# 01_Leonardo_Rev3d.net
KiCad netlist of a schematic drawn in Altium Designer
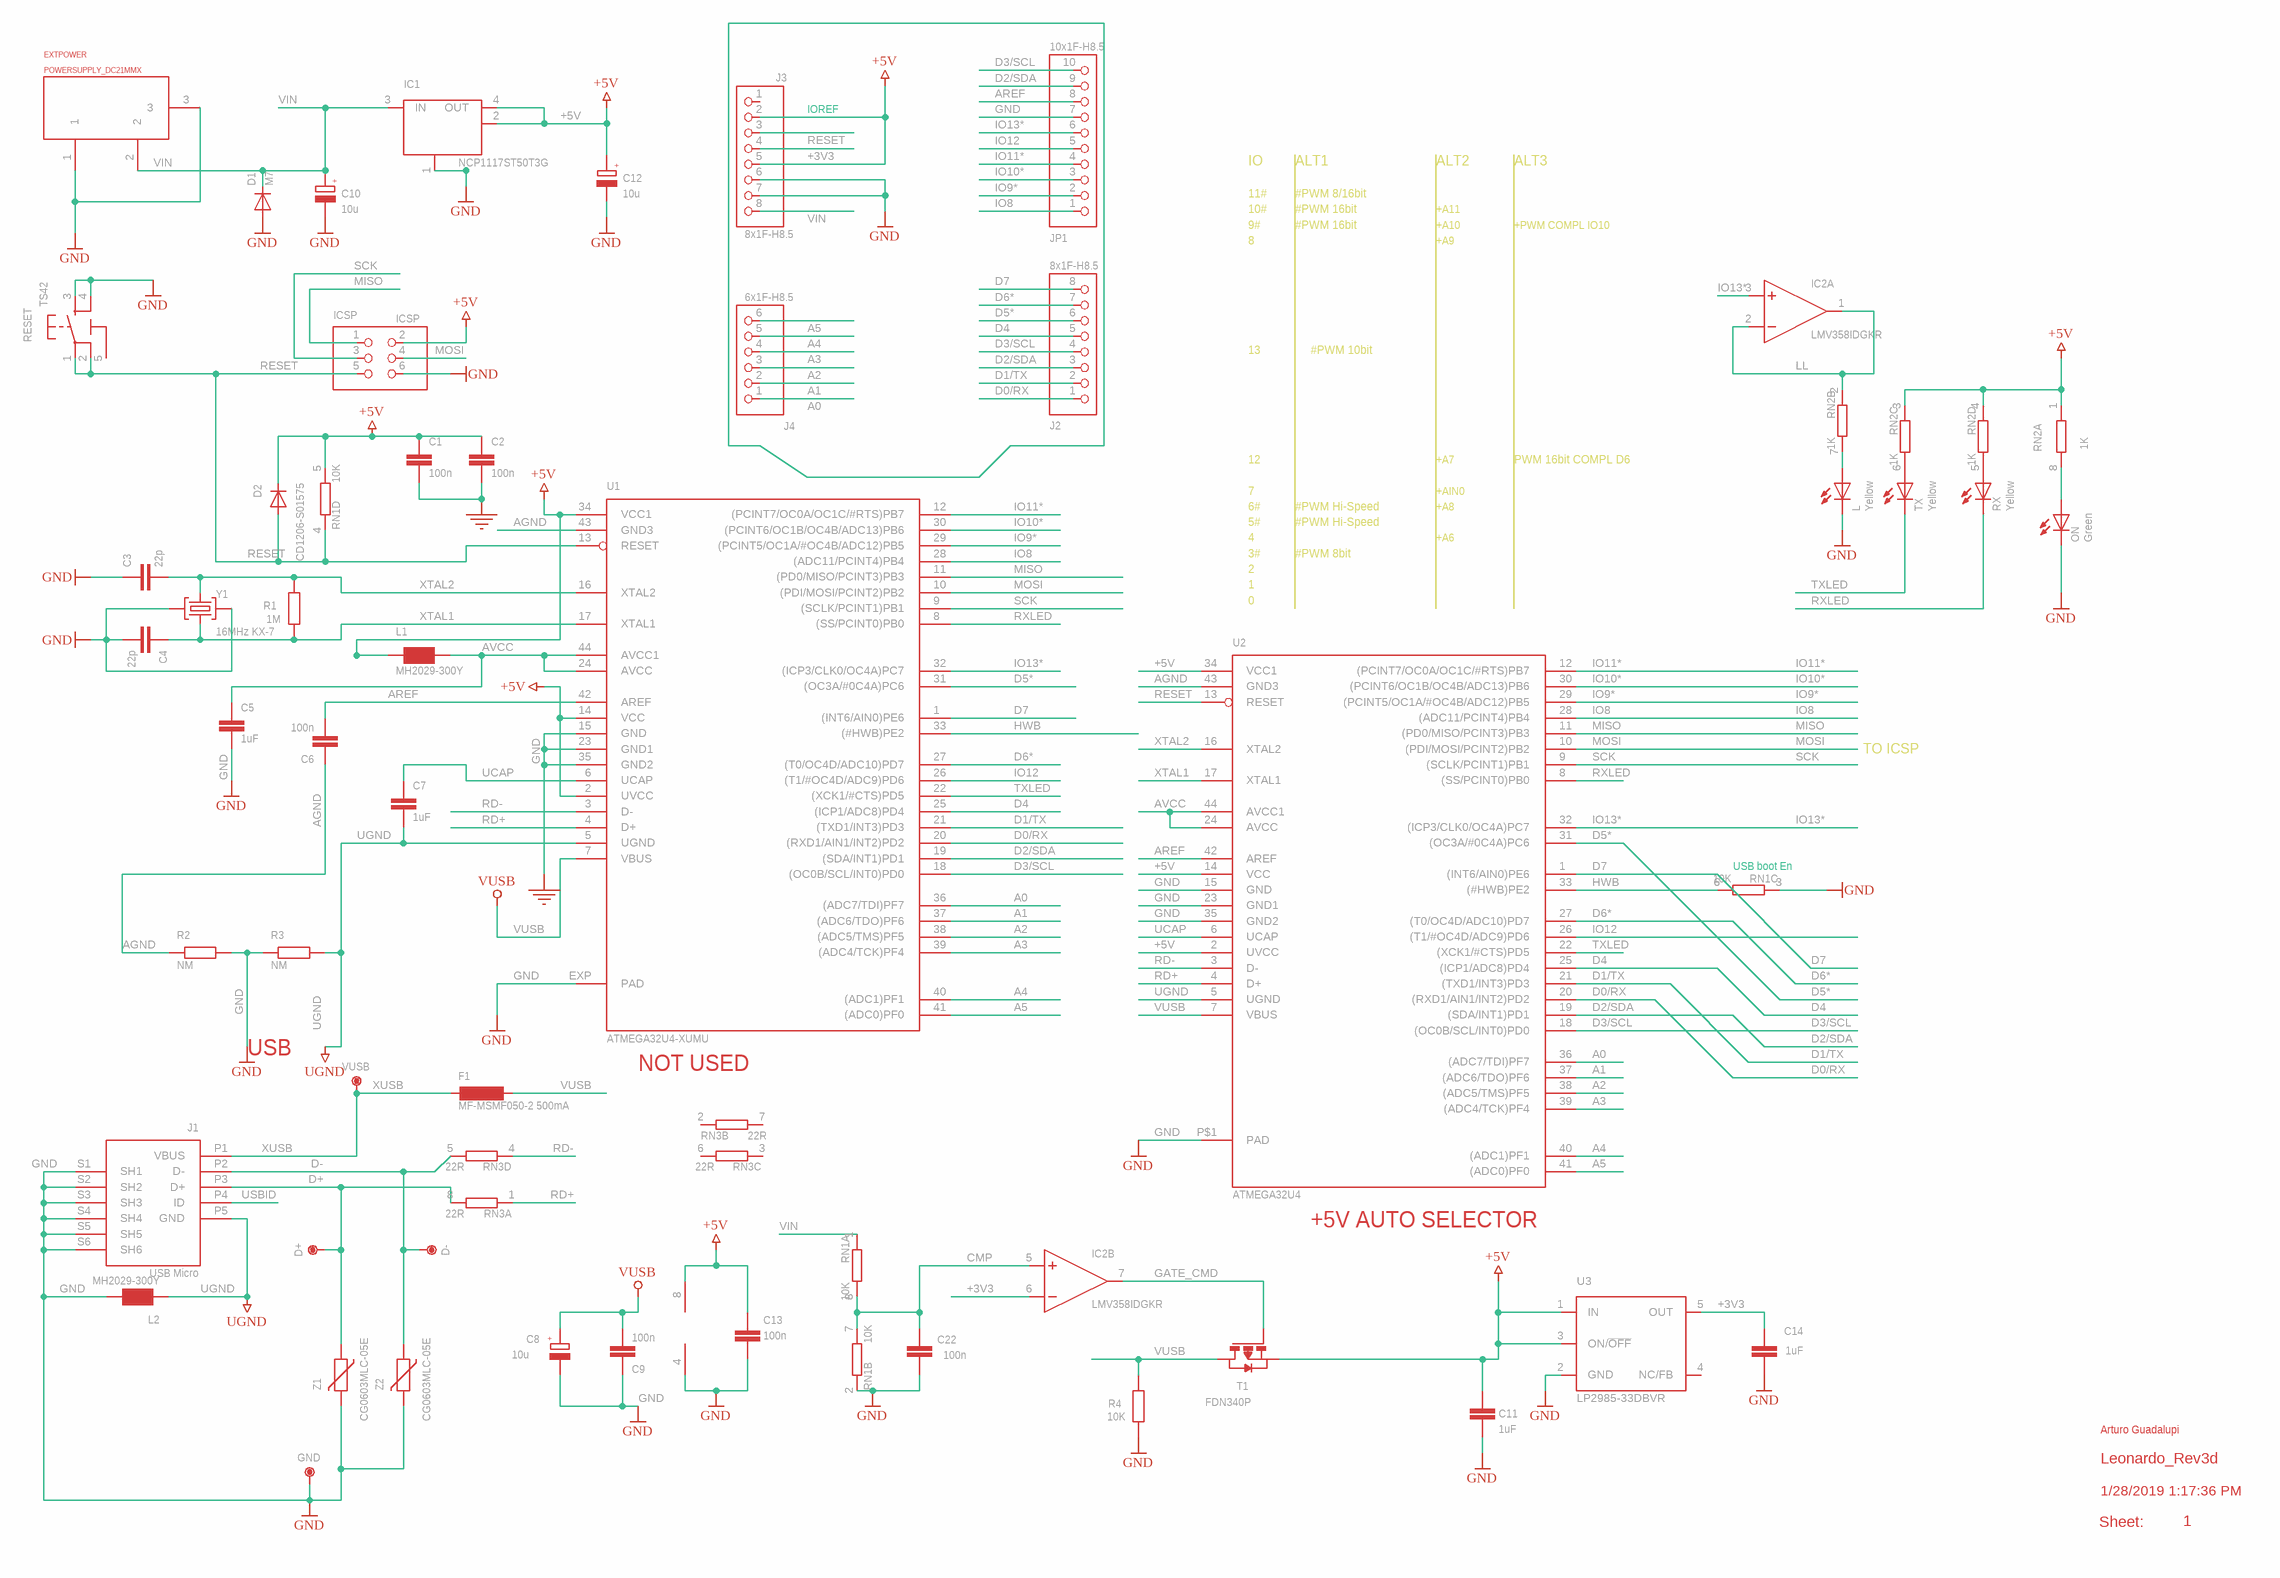
[diagram p0: 01.Leonardo_Rev3d.SchDoc]

(export (version "E")
  (design (tool "Eeschema 10.0.6"))
  (components
    (comp (ref "C1")
      (value "100n")
      (footprint "C0603-ROUND")
      (description "CAPACITOR, European symbol")
      (libsource (lib "") (part "C-EUC0603_2"))
    )
    (comp (ref "C2")
      (value "100n")
      (footprint "C0603-ROUND")
      (description "CAPACITOR, European symbol")
      (libsource (lib "") (part "C-EUC0603_2"))
    )
    (comp (ref "C3")
      (value "22p")
      (footprint "C0603-ROUND")
      (description "CAPACITOR, European symbol")
      (libsource (lib "") (part "C-EUC0603_1"))
    )
    (comp (ref "C4")
      (value "22p")
      (footprint "C0603-ROUND")
      (description "CAPACITOR, European symbol")
      (libsource (lib "") (part "C-EUC0603_3"))
    )
    (comp (ref "C5")
      (value "1uF")
      (footprint "C0603-ROUND")
      (description "CAPACITOR, European symbol")
      (libsource (lib "") (part "C-EUC0603_2"))
    )
    (comp (ref "C6")
      (value "100n")
      (footprint "C0603-ROUND")
      (description "CAPACITOR, European symbol")
      (libsource (lib "SmartPrj") (part "C-EUC0603"))
    )
    (comp (ref "C7")
      (value "1uF")
      (footprint "C0603-ROUND")
      (description "CAPACITOR, European symbol")
      (libsource (lib "") (part "C-EUC0603_2"))
    )
    (comp (ref "C8")
      (value "10u")
      (footprint "SMC_B")
      (description "POLARIZED CAPACITOR, European symbol")
      (fields (field (name "+") "+"))
      (libsource (lib "") (part "CPOL-EUSMCB_1"))
    )
    (comp (ref "C9")
      (value "100n")
      (footprint "C0603-ROUND")
      (description "CAPACITOR, European symbol")
      (libsource (lib "") (part "C-EUC0603_1"))
    )
    (comp (ref "C10")
      (value "10u")
      (footprint "SMC_B")
      (description "POLARIZED CAPACITOR, European symbol")
      (fields (field (name "+") "+"))
      (libsource (lib "rcl") (part "CPOL-EUSMCB"))
    )
    (comp (ref "C11")
      (value "1uF")
      (footprint "C0603-ROUND")
      (description "CAPACITOR, European symbol")
      (libsource (lib "") (part "C-EUC0603_1"))
    )
    (comp (ref "C12")
      (value "10u")
      (footprint "SMC_B")
      (description "POLARIZED CAPACITOR, European symbol")
      (fields (field (name "+") "+"))
      (libsource (lib "rcl") (part "CPOL-EUSMCB"))
    )
    (comp (ref "C13")
      (value "100n")
      (footprint "C0603-ROUND")
      (description "CAPACITOR, European symbol")
      (libsource (lib "") (part "C-EUC0603_2"))
    )
    (comp (ref "C14")
      (value "1uF")
      (footprint "C0603-ROUND")
      (description "CAPACITOR, European symbol")
      (libsource (lib "SmartPrj") (part "C-EUC0603"))
    )
    (comp (ref "C22")
      (value "100n")
      (footprint "C0603-ROUND")
      (description "CAPACITOR, European symbol")
      (libsource (lib "") (part "C-EUC0603_1"))
    )
    (comp (ref "D+")
      (value "DNP")
      (footprint "TP-1.00MM")
      (description "Testpoint")
      (libsource (lib "Arduino-utility") (part "TPTP-1.00MM"))
    )
    (comp (ref "D-")
      (value "DNP")
      (footprint "TP-1.00MM")
      (description "Testpoint")
      (libsource (lib "Arduino-utility") (part "TPTP-1.00MM"))
    )
    (comp (ref "D1")
      (value "M7")
      (footprint "SMB")
      (description "DIODE")
      (libsource (lib "diode") (part "DIODE-SMB"))
    )
    (comp (ref "D2")
      (value "CD1206-S01575")
      (footprint "MINIMELF")
      (description "DIODE")
      (libsource (lib "diode") (part "DIODE-MINIMELF"))
    )
    (comp (ref "EXTPOWER")
      (value "POWERSUPPLY_DC21MMX")
      (footprint "POWERSUPPLY_DC-21MM")
      (libsource (lib "SmartPrj") (part "POWERSUPPLY_DC21MMX"))
    )
    (comp (ref "F1")
      (value "MF-MSMF050-2 500mA")
      (footprint "L1812")
      (description "INDUCTOR, European symbol")
      (libsource (lib "rcl") (part "L-EUL1812"))
    )
    (comp (ref "GND")
      (value "DNP")
      (footprint "TP-1.00MM")
      (description "Testpoint")
      (libsource (lib "Arduino-utility") (part "TPTP-1.00MM"))
    )
    (comp (ref "IC1")
      (value "NCP1117ST50T3G")
      (footprint "SOT223")
      (libsource (lib "linear") (part "MC33269ST*"))
    )
    (comp (ref "IC2")
      (value "LMV358IDGKR")
      (footprint "MSOP08")
      (libsource (lib "linear") (part "LMV358?*MM"))
    )
    (comp (ref "ICSP")
      (value "ICSP")
      (footprint "2X03")
      (description "PIN HEADER")
      (libsource (lib "SmartPrj") (part "PINHD-2X3"))
    )
    (comp (ref "J1")
      (value "USB Micro")
      (footprint "CON2_USB_MICRO_B_AT")
      (fields (field (name "MANUFACTURER") "FCI"))
      (libsource (lib "Arduino-connectors") (part "USB-MICRO-LEGACY"))
    )
    (comp (ref "J2")
      (value "8x1F-H8.5")
      (footprint "1X08")
      (description "PIN HEADER")
      (libsource (lib "SmartPrj") (part "PINHD-1X8"))
    )
    (comp (ref "J3")
      (value "8x1F-H8.5")
      (footprint "1X08")
      (description "PIN HEADER")
      (libsource (lib "SmartPrj") (part "PINHD-1X8"))
    )
    (comp (ref "J4")
      (value "6x1F-H8.5")
      (footprint "1X06")
      (description "PIN HEADER")
      (libsource (lib "SmartPrj") (part "PINHD-1X6"))
    )
    (comp (ref "JP1")
      (value "10x1F-H8.5")
      (footprint "1X10")
      (description "PIN HEADER")
      (libsource (lib "SmartPrj") (part "PINHD-1X10"))
    )
    (comp (ref "L")
      (value "Yellow")
      (footprint "CHIPLED_0805")
      (libsource (lib "led") (part "LEDCHIPLED_0805"))
    )
    (comp (ref "L1") (value "MH2029-300Y") (footprint "0805") (libsource (lib "") (part "WE-CBF_0805_1")))
    (comp (ref "L2")
      (value "MH2029-300Y")
      (footprint "0805")
      (libsource (lib "wuerth-elektronik") (part "WE-CBF_0805"))
    )
    (comp (ref "ON")
      (value "Green")
      (footprint "CHIPLED_0805")
      (libsource (lib "led") (part "LEDCHIPLED_0805"))
    )
    (comp (ref "R1")
      (value "1M")
      (footprint "R0603-ROUND")
      (description "RESISTOR, European symbol")
      (libsource (lib "SmartPrj") (part "R-EU_R0603"))
    )
    (comp (ref "R2")
      (value "NM")
      (footprint "R0402")
      (description "RESISTOR, European symbol")
      (libsource (lib "SmartPrj") (part "R-EU_R0402"))
    )
    (comp (ref "R3")
      (value "NM")
      (footprint "R0402")
      (description "RESISTOR, European symbol")
      (libsource (lib "SmartPrj") (part "R-EU_R0402"))
    )
    (comp (ref "R4")
      (value "10K")
      (footprint "R0603-ROUND")
      (description "RESISTOR, European symbol")
      (libsource (lib "SmartPrj") (part "R-EU_R0603"))
    )
    (comp (ref "RESET")
      (value "TS42")
      (footprint "TS42")
      (description "TS42 Dongnan Electronics Tact switch VDC 12V - 50mA")
      (libsource (lib "SmartPrj") (part "TS42"))
    )
    (comp (ref "RN1")
      (value "10K")
      (footprint "CAY16")
      (description "Array Chip Resistor   Source: RS Component / Phycomp")
      (fields (field (name "LIBRARYNAME") "resistor-dil"))
      (libsource (lib "resistor-dil") (part "4R-NCAY16"))
    )
    (comp (ref "RN2")
      (value "1K")
      (footprint "CAY16")
      (description "Array Chip Resistor   Source: RS Component / Phycomp")
      (fields (field (name "LIBRARYNAME") "resistor-dil"))
      (libsource (lib "resistor-dil") (part "4R-NCAY16"))
    )
    (comp (ref "RN3")
      (value "22R")
      (footprint "CAY16")
      (description "Array Chip Resistor   Source: RS Component / Phycomp")
      (fields (field (name "LIBRARYNAME") "resistor-dil"))
      (libsource (lib "resistor-dil") (part "4R-NCAY16"))
    )
    (comp (ref "RX")
      (value "Yellow")
      (footprint "CHIPLED_0805")
      (libsource (lib "led") (part "LEDCHIPLED_0805"))
    )
    (comp (ref "T1")
      (value "FDN340P")
      (footprint "SOT-23")
      (description "MOS FET")
      (libsource (lib "zetex") (part "PMOSSOT23"))
    )
    (comp (ref "TX")
      (value "Yellow")
      (footprint "CHIPLED_0805")
      (libsource (lib "led") (part "LEDCHIPLED_0805"))
    )
    (comp (ref "U1")
      (value "ATMEGA32U4-XUMU")
      (footprint "QFN44ML7X7")
      (libsource (lib "SmartPrj") (part "ATMEGA32U4-XUMU"))
    )
    (comp (ref "U2")
      (value "ATMEGA32U4")
      (footprint "TQFP44-PAD")
      (libsource (lib "SmartPrj") (part "ATMEGA32U4-XUAU"))
    )
    (comp (ref "U3")
      (value "LP2985-33DBVR")
      (footprint "SOT23-DBV")
      (libsource (lib "SmartPrj") (part "LP2985-XXDBVR"))
    )
    (comp (ref "VUSB")
      (value "DNP")
      (footprint "TP-1.00MM")
      (description "Testpoint")
      (libsource (lib "Arduino-utility") (part "TPTP-1.00MM"))
    )
    (comp (ref "Y1")
      (value "16MHz KX-7")
      (footprint "CRYSTAL-3.2-2.5")
      (libsource (lib "SmartPrj") (part "CRYSTAL-3.2-2.5"))
    )
    (comp (ref "Z1")
      (value "CG0603MLC-05E")
      (footprint "CT/CN0603")
      (description "VARISTOR")
      (libsource (lib "varistor") (part "VARISTORCN0603"))
    )
    (comp (ref "Z2")
      (value "CG0603MLC-05E")
      (footprint "CT/CN0603")
      (description "VARISTOR")
      (libsource (lib "varistor") (part "VARISTORCN0603"))
    )
  )
  (nets
    (net (code "1") (name "+5V") (class "Default")
      (node (ref "C1") (pin "1") (pinfunction "1_1") (pintype "passive"))
      (node (ref "C11") (pin "2") (pinfunction "2_2") (pintype "passive"))
      (node (ref "C12") (pin "+") (pinfunction "+_+") (pintype "passive"))
      (node (ref "C13") (pin "1") (pinfunction "1_1") (pintype "passive"))
      (node (ref "C2") (pin "1") (pinfunction "1_1") (pintype "passive"))
      (node (ref "D2") (pin "C") (pinfunction "C_C") (pintype "passive"))
      (node (ref "IC1") (pin "2") (pinfunction "OUT_2") (pintype "passive"))
      (node (ref "IC1") (pin "4") (pinfunction "OUT_4") (pintype "passive"))
      (node (ref "IC2") (pin "8") (pinfunction "V+_8") (pintype "passive"))
      (node (ref "ICSP") (pin "2") (pinfunction "2_2") (pintype "passive"))
      (node (ref "J3") (pin "2") (pinfunction "2_2") (pintype "passive"))
      (node (ref "J3") (pin "5") (pinfunction "5_5") (pintype "passive"))
      (node (ref "L1") (pin "1") (pinfunction "1_1") (pintype "passive"))
      (node (ref "RN1") (pin "5") (pinfunction "2_5") (pintype "passive"))
      (node (ref "RN2") (pin "1") (pinfunction "1_1") (pintype "passive"))
      (node (ref "RN2") (pin "3") (pinfunction "1_3") (pintype "passive"))
      (node (ref "RN2") (pin "4") (pinfunction "1_4") (pintype "passive"))
      (node (ref "T1") (pin "2") (pinfunction "S_2") (pintype "passive"))
      (node (ref "U1") (pin "14") (pinfunction "VCC_14") (pintype "passive"))
      (node (ref "U1") (pin "2") (pinfunction "UVCC_2") (pintype "passive"))
      (node (ref "U1") (pin "34") (pinfunction "VCC1_34") (pintype "passive"))
      (node (ref "U2") (pin "14") (pinfunction "VCC_14") (pintype "passive"))
      (node (ref "U2") (pin "2") (pinfunction "UVCC_2") (pintype "passive"))
      (node (ref "U2") (pin "34") (pinfunction "VCC1_34") (pintype "passive"))
      (node (ref "U3") (pin "1") (pinfunction "IN_1") (pintype "passive"))
      (node (ref "U3") (pin "3") (pinfunction "ON/~{OFF}_3") (pintype "passive"))
    )
    (net (code "2") (name "/+3V3") (class "Default")
      (node (ref "C14") (pin "2") (pinfunction "2_2") (pintype "passive"))
      (node (ref "IC2") (pin "6") (pinfunction "-IN_6") (pintype "passive"))
      (node (ref "J3") (pin "4") (pinfunction "4_4") (pintype "passive"))
      (node (ref "U3") (pin "5") (pinfunction "OUT_5") (pintype "passive"))
    )
    (net (code "3") (name "/A0") (class "Default")
      (node (ref "J4") (pin "1") (pinfunction "1_1") (pintype "passive"))
      (node (ref "U1") (pin "36") (pinfunction "(ADC7/TDI)PF7_36") (pintype "passive"))
      (node (ref "U2") (pin "36") (pinfunction "(ADC7/TDI)PF7_36") (pintype "passive"))
    )
    (net (code "4") (name "/A1") (class "Default")
      (node (ref "J4") (pin "2") (pinfunction "2_2") (pintype "passive"))
      (node (ref "U1") (pin "37") (pinfunction "(ADC6/TDO)PF6_37") (pintype "passive"))
      (node (ref "U2") (pin "37") (pinfunction "(ADC6/TDO)PF6_37") (pintype "passive"))
    )
    (net (code "5") (name "/A2") (class "Default")
      (node (ref "J4") (pin "3") (pinfunction "3_3") (pintype "passive"))
      (node (ref "U1") (pin "38") (pinfunction "(ADC5/TMS)PF5_38") (pintype "passive"))
      (node (ref "U2") (pin "38") (pinfunction "(ADC5/TMS)PF5_38") (pintype "passive"))
    )
    (net (code "6") (name "/A3") (class "Default")
      (node (ref "J4") (pin "4") (pinfunction "4_4") (pintype "passive"))
      (node (ref "U1") (pin "39") (pinfunction "(ADC4/TCK)PF4_39") (pintype "passive"))
      (node (ref "U2") (pin "39") (pinfunction "(ADC4/TCK)PF4_39") (pintype "passive"))
    )
    (net (code "7") (name "/A4") (class "Default")
      (node (ref "J4") (pin "5") (pinfunction "5_5") (pintype "passive"))
      (node (ref "U1") (pin "40") (pinfunction "(ADC1)PF1_40") (pintype "passive"))
      (node (ref "U2") (pin "40") (pinfunction "(ADC1)PF1_40") (pintype "passive"))
    )
    (net (code "8") (name "/A5") (class "Default")
      (node (ref "J4") (pin "6") (pinfunction "6_6") (pintype "passive"))
      (node (ref "U1") (pin "41") (pinfunction "(ADC0)PF0_41") (pintype "passive"))
      (node (ref "U2") (pin "41") (pinfunction "(ADC0)PF0_41") (pintype "passive"))
    )
    (net (code "9") (name "/AGND") (class "Default")
      (node (ref "C6") (pin "1") (pinfunction "1_1") (pintype "passive"))
      (node (ref "R2") (pin "1") (pinfunction "1_1") (pintype "passive"))
      (node (ref "U1") (pin "43") (pinfunction "GND3_43") (pintype "passive"))
      (node (ref "U2") (pin "43") (pinfunction "GND3_43") (pintype "passive"))
    )
    (net (code "10") (name "/AREF") (class "Default")
      (node (ref "C6") (pin "2") (pinfunction "2_2") (pintype "passive"))
      (node (ref "JP1") (pin "8") (pinfunction "8_8") (pintype "passive"))
      (node (ref "U1") (pin "42") (pinfunction "AREF_42") (pintype "passive"))
      (node (ref "U2") (pin "42") (pinfunction "AREF_42") (pintype "passive"))
    )
    (net (code "11") (name "/AVCC") (class "Default")
      (node (ref "C5") (pin "1") (pinfunction "1_1") (pintype "passive"))
      (node (ref "L1") (pin "2") (pinfunction "2_2") (pintype "passive"))
      (node (ref "U1") (pin "24") (pinfunction "AVCC_24") (pintype "passive"))
      (node (ref "U1") (pin "44") (pinfunction "AVCC1_44") (pintype "passive"))
      (node (ref "U2") (pin "24") (pinfunction "AVCC_24") (pintype "passive"))
      (node (ref "U2") (pin "44") (pinfunction "AVCC1_44") (pintype "passive"))
    )
    (net (code "12") (name "/CMP") (class "Default")
      (node (ref "C22") (pin "2") (pinfunction "2_2") (pintype "passive"))
      (node (ref "IC2") (pin "5") (pinfunction "+IN_5") (pintype "passive"))
      (node (ref "RN1") (pin "7") (pinfunction "2_7") (pintype "passive"))
      (node (ref "RN1") (pin "8") (pinfunction "2_8") (pintype "passive"))
    )
    (net (code "13") (name "/D+") (class "Default")
      (node (ref "D+") (pin "X") (pinfunction "P$1_X") (pintype "passive"))
      (node (ref "J1") (pin "P3") (pinfunction "D+_P3") (pintype "passive"))
      (node (ref "RN3") (pin "8") (pinfunction "2_8") (pintype "passive"))
      (node (ref "Z1") (pin "1") (pinfunction "1_1") (pintype "passive"))
    )
    (net (code "14") (name "/D-") (class "Default")
      (node (ref "D-") (pin "X") (pinfunction "P$1_X") (pintype "passive"))
      (node (ref "J1") (pin "P2") (pinfunction "D-_P2") (pintype "passive"))
      (node (ref "RN3") (pin "5") (pinfunction "2_5") (pintype "passive"))
      (node (ref "Z2") (pin "1") (pinfunction "1_1") (pintype "passive"))
    )
    (net (code "15") (name "/D0{slash}RX") (class "Default")
      (node (ref "J2") (pin "1") (pinfunction "1_1") (pintype "passive"))
      (node (ref "U1") (pin "20") (pinfunction "(RXD1/AIN1/INT2)PD2_20") (pintype "passive"))
      (node (ref "U2") (pin "20") (pinfunction "(RXD1/AIN1/INT2)PD2_20") (pintype "passive"))
    )
    (net (code "16") (name "/D1{slash}TX") (class "Default")
      (node (ref "J2") (pin "2") (pinfunction "2_2") (pintype "passive"))
      (node (ref "U1") (pin "21") (pinfunction "(TXD1/INT3)PD3_21") (pintype "passive"))
      (node (ref "U2") (pin "21") (pinfunction "(TXD1/INT3)PD3_21") (pintype "passive"))
    )
    (net (code "17") (name "/D2{slash}SDA") (class "Default")
      (node (ref "J2") (pin "3") (pinfunction "3_3") (pintype "passive"))
      (node (ref "JP1") (pin "9") (pinfunction "9_9") (pintype "passive"))
      (node (ref "U1") (pin "19") (pinfunction "(SDA/INT1)PD1_19") (pintype "passive"))
      (node (ref "U2") (pin "19") (pinfunction "(SDA/INT1)PD1_19") (pintype "passive"))
    )
    (net (code "18") (name "/D3{slash}SCL") (class "Default")
      (node (ref "J2") (pin "4") (pinfunction "4_4") (pintype "passive"))
      (node (ref "JP1") (pin "10") (pinfunction "10_10") (pintype "passive"))
      (node (ref "U1") (pin "18") (pinfunction "(OC0B/SCL/INT0)PD0_18") (pintype "passive"))
      (node (ref "U2") (pin "18") (pinfunction "(OC0B/SCL/INT0)PD0_18") (pintype "passive"))
    )
    (net (code "19") (name "/D4") (class "Default")
      (node (ref "J2") (pin "5") (pinfunction "5_5") (pintype "passive"))
      (node (ref "U1") (pin "25") (pinfunction "(ICP1/ADC8)PD4_25") (pintype "passive"))
      (node (ref "U2") (pin "25") (pinfunction "(ICP1/ADC8)PD4_25") (pintype "passive"))
    )
    (net (code "20") (name "/D5*") (class "Default")
      (node (ref "J2") (pin "6") (pinfunction "6_6") (pintype "passive"))
      (node (ref "U1") (pin "31") (pinfunction "(OC3A/#0C4A)PC6_31") (pintype "passive"))
      (node (ref "U2") (pin "31") (pinfunction "(OC3A/#0C4A)PC6_31") (pintype "passive"))
    )
    (net (code "21") (name "/D6*") (class "Default")
      (node (ref "J2") (pin "7") (pinfunction "7_7") (pintype "passive"))
      (node (ref "U1") (pin "27") (pinfunction "(T0/OC4D/ADC10)PD7_27") (pintype "passive"))
      (node (ref "U2") (pin "27") (pinfunction "(T0/OC4D/ADC10)PD7_27") (pintype "passive"))
    )
    (net (code "22") (name "/D7") (class "Default")
      (node (ref "J2") (pin "8") (pinfunction "8_8") (pintype "passive"))
      (node (ref "U1") (pin "1") (pinfunction "(INT6/AIN0)PE6_1") (pintype "passive"))
      (node (ref "U2") (pin "1") (pinfunction "(INT6/AIN0)PE6_1") (pintype "passive"))
    )
    (net (code "23") (name "/GATE_CMD") (class "Default")
      (node (ref "IC2") (pin "7") (pinfunction "OUT_7") (pintype "passive"))
      (node (ref "T1") (pin "3") (pinfunction "G_3") (pintype "passive"))
    )
    (net (code "24") (name "/HWB") (class "Default")
      (node (ref "RN1") (pin "6") (pinfunction "2_6") (pintype "passive"))
      (node (ref "U1") (pin "33") (pinfunction "(#HWB)PE2_33") (pintype "passive"))
      (node (ref "U2") (pin "33") (pinfunction "(#HWB)PE2_33") (pintype "passive"))
    )
    (net (code "25") (name "/IO8") (class "Default")
      (node (ref "JP1") (pin "1") (pinfunction "1_1") (pintype "passive"))
      (node (ref "U1") (pin "28") (pinfunction "(ADC11/PCINT4)PB4_28") (pintype "passive"))
      (node (ref "U2") (pin "28") (pinfunction "(ADC11/PCINT4)PB4_28") (pintype "passive"))
    )
    (net (code "26") (name "/IO9*") (class "Default")
      (node (ref "JP1") (pin "2") (pinfunction "2_2") (pintype "passive"))
      (node (ref "U1") (pin "29") (pinfunction "(PCINT5/OC1A/#OC4B/ADC12)PB5_29") (pintype "passive"))
      (node (ref "U2") (pin "29") (pinfunction "(PCINT5/OC1A/#OC4B/ADC12)PB5_29") (pintype "passive"))
    )
    (net (code "27") (name "/IO10*") (class "Default")
      (node (ref "JP1") (pin "3") (pinfunction "3_3") (pintype "passive"))
      (node (ref "U1") (pin "30") (pinfunction "(PCINT6/OC1B/OC4B/ADC13)PB6_30") (pintype "passive"))
      (node (ref "U2") (pin "30") (pinfunction "(PCINT6/OC1B/OC4B/ADC13)PB6_30") (pintype "passive"))
    )
    (net (code "28") (name "/IO11*") (class "Default")
      (node (ref "JP1") (pin "4") (pinfunction "4_4") (pintype "passive"))
      (node (ref "U1") (pin "12") (pinfunction "(PCINT7/OC0A/OC1C/#RTS)PB7_12") (pintype "passive"))
      (node (ref "U2") (pin "12") (pinfunction "(PCINT7/OC0A/OC1C/#RTS)PB7_12") (pintype "passive"))
    )
    (net (code "29") (name "/IO12") (class "Default")
      (node (ref "JP1") (pin "5") (pinfunction "5_5") (pintype "passive"))
      (node (ref "U1") (pin "26") (pinfunction "(T1/#OC4D/ADC9)PD6_26") (pintype "passive"))
      (node (ref "U2") (pin "26") (pinfunction "(T1/#OC4D/ADC9)PD6_26") (pintype "passive"))
    )
    (net (code "30") (name "/IO13*") (class "Default")
      (node (ref "IC2") (pin "3") (pinfunction "+IN_3") (pintype "passive"))
      (node (ref "JP1") (pin "6") (pinfunction "6_6") (pintype "passive"))
      (node (ref "U1") (pin "32") (pinfunction "(ICP3/CLK0/OC4A)PC7_32") (pintype "passive"))
      (node (ref "U2") (pin "32") (pinfunction "(ICP3/CLK0/OC4A)PC7_32") (pintype "passive"))
    )
    (net (code "31") (name "/LL") (class "Default")
      (node (ref "IC2") (pin "1") (pinfunction "OUT_1") (pintype "passive"))
      (node (ref "IC2") (pin "2") (pinfunction "-IN_2") (pintype "passive"))
      (node (ref "RN2") (pin "2") (pinfunction "1_2") (pintype "passive"))
    )
    (net (code "32") (name "/MISO") (class "Default")
      (node (ref "ICSP") (pin "1") (pinfunction "1_1") (pintype "passive"))
      (node (ref "U1") (pin "11") (pinfunction "(PD0/MISO/PCINT3)PB3_11") (pintype "passive"))
      (node (ref "U2") (pin "11") (pinfunction "(PD0/MISO/PCINT3)PB3_11") (pintype "passive"))
    )
    (net (code "33") (name "/MOSI") (class "Default")
      (node (ref "ICSP") (pin "4") (pinfunction "4_4") (pintype "passive"))
      (node (ref "U1") (pin "10") (pinfunction "(PDI/MOSI/PCINT2)PB2_10") (pintype "passive"))
      (node (ref "U2") (pin "10") (pinfunction "(PDI/MOSI/PCINT2)PB2_10") (pintype "passive"))
    )
    (net (code "34") (name "/RD+") (class "Default")
      (node (ref "RN3") (pin "1") (pinfunction "1_1") (pintype "passive"))
      (node (ref "U1") (pin "4") (pinfunction "D+_4") (pintype "passive"))
      (node (ref "U2") (pin "4") (pinfunction "D+_4") (pintype "passive"))
    )
    (net (code "35") (name "/RD-") (class "Default")
      (node (ref "RN3") (pin "4") (pinfunction "1_4") (pintype "passive"))
      (node (ref "U1") (pin "3") (pinfunction "D-_3") (pintype "passive"))
      (node (ref "U2") (pin "3") (pinfunction "D-_3") (pintype "passive"))
    )
    (net (code "36") (name "/RESET") (class "Default")
      (node (ref "D2") (pin "A") (pinfunction "A_A") (pintype "passive"))
      (node (ref "ICSP") (pin "5") (pinfunction "5_5") (pintype "passive"))
      (node (ref "J3") (pin "3") (pinfunction "3_3") (pintype "passive"))
      (node (ref "RESET") (pin "1") (pinfunction "1_1") (pintype "passive"))
      (node (ref "RESET") (pin "2") (pinfunction "2_2") (pintype "passive"))
      (node (ref "RN1") (pin "4") (pinfunction "1_4") (pintype "passive"))
      (node (ref "U1") (pin "13") (pinfunction "RESET_13") (pintype "passive"))
      (node (ref "U2") (pin "13") (pinfunction "RESET_13") (pintype "passive"))
    )
    (net (code "37") (name "/RXLED") (class "Default")
      (node (ref "RX") (pin "C") (pinfunction "C_C") (pintype "passive"))
      (node (ref "U1") (pin "8") (pinfunction "(SS/PCINT0)PB0_8") (pintype "passive"))
      (node (ref "U2") (pin "8") (pinfunction "(SS/PCINT0)PB0_8") (pintype "passive"))
    )
    (net (code "38") (name "/SCK") (class "Default")
      (node (ref "ICSP") (pin "3") (pinfunction "3_3") (pintype "passive"))
      (node (ref "U1") (pin "9") (pinfunction "(SCLK/PCINT1)PB1_9") (pintype "passive"))
      (node (ref "U2") (pin "9") (pinfunction "(SCLK/PCINT1)PB1_9") (pintype "passive"))
    )
    (net (code "39") (name "/TXLED") (class "Default")
      (node (ref "TX") (pin "C") (pinfunction "C_C") (pintype "passive"))
      (node (ref "U1") (pin "22") (pinfunction "(XCK1/#CTS)PD5_22") (pintype "passive"))
      (node (ref "U2") (pin "22") (pinfunction "(XCK1/#CTS)PD5_22") (pintype "passive"))
    )
    (net (code "40") (name "/UCAP") (class "Default")
      (node (ref "C7") (pin "1") (pinfunction "1_1") (pintype "passive"))
      (node (ref "U1") (pin "6") (pinfunction "UCAP_6") (pintype "passive"))
      (node (ref "U2") (pin "6") (pinfunction "UCAP_6") (pintype "passive"))
    )
    (net (code "41") (name "/USBID") (class "Default")
      (node (ref "J1") (pin "P4") (pinfunction "ID_P4") (pintype "passive"))
    )
    (net (code "42") (name "/VIN") (class "Default")
      (node (ref "C10") (pin "+") (pinfunction "+_+") (pintype "passive"))
      (node (ref "D1") (pin "C") (pinfunction "C_C") (pintype "passive"))
      (node (ref "EXTPOWER") (pin "2") (pinfunction "2_2") (pintype "passive"))
      (node (ref "IC1") (pin "3") (pinfunction "IN_3") (pintype "passive"))
      (node (ref "J3") (pin "8") (pinfunction "8_8") (pintype "passive"))
      (node (ref "RN1") (pin "1") (pinfunction "1_1") (pintype "passive"))
    )
    (net (code "43") (name "/XTAL1") (class "Default")
      (node (ref "C4") (pin "1") (pinfunction "1_1") (pintype "passive"))
      (node (ref "R1") (pin "1") (pinfunction "1_1") (pintype "passive"))
      (node (ref "U1") (pin "17") (pinfunction "XTAL1_17") (pintype "passive"))
      (node (ref "U2") (pin "17") (pinfunction "XTAL1_17") (pintype "passive"))
      (node (ref "Y1") (pin "1") (pinfunction "C1_1") (pintype "passive"))
    )
    (net (code "44") (name "/XTAL2") (class "Default")
      (node (ref "C3") (pin "2") (pinfunction "2_2") (pintype "passive"))
      (node (ref "R1") (pin "2") (pinfunction "2_2") (pintype "passive"))
      (node (ref "U1") (pin "16") (pinfunction "XTAL2_16") (pintype "passive"))
      (node (ref "U2") (pin "16") (pinfunction "XTAL2_16") (pintype "passive"))
      (node (ref "Y1") (pin "3") (pinfunction "C2_3") (pintype "passive"))
    )
    (net (code "45") (name "/XUSB") (class "Default")
      (node (ref "F1") (pin "2") (pinfunction "2_2") (pintype "passive"))
      (node (ref "J1") (pin "P1") (pinfunction "VBUS_P1") (pintype "passive"))
      (node (ref "VUSB") (pin "X") (pinfunction "P$1_X") (pintype "passive"))
    )
    (net (code "46") (name "GND") (class "Default")
      (node (ref "C1") (pin "2") (pinfunction "2_2") (pintype "passive"))
      (node (ref "C10") (pin "-") (pinfunction "-_-") (pintype "passive"))
      (node (ref "C11") (pin "1") (pinfunction "1_1") (pintype "passive"))
      (node (ref "C12") (pin "-") (pinfunction "-_-") (pintype "passive"))
      (node (ref "C13") (pin "2") (pinfunction "2_2") (pintype "passive"))
      (node (ref "C14") (pin "1") (pinfunction "1_1") (pintype "passive"))
      (node (ref "C2") (pin "2") (pinfunction "2_2") (pintype "passive"))
      (node (ref "C22") (pin "1") (pinfunction "1_1") (pintype "passive"))
      (node (ref "C3") (pin "1") (pinfunction "1_1") (pintype "passive"))
      (node (ref "C4") (pin "2") (pinfunction "2_2") (pintype "passive"))
      (node (ref "C5") (pin "2") (pinfunction "2_2") (pintype "passive"))
      (node (ref "C8") (pin "-") (pinfunction "-_-") (pintype "passive"))
      (node (ref "C9") (pin "1") (pinfunction "1_1") (pintype "passive"))
      (node (ref "D1") (pin "A") (pinfunction "A_A") (pintype "passive"))
      (node (ref "EXTPOWER") (pin "1") (pinfunction "1_1") (pintype "passive"))
      (node (ref "EXTPOWER") (pin "3") (pinfunction "3_3") (pintype "passive"))
      (node (ref "GND") (pin "X") (pinfunction "P$1_X") (pintype "passive"))
      (node (ref "IC1") (pin "1") (pinfunction "GND/ADJ_1") (pintype "passive"))
      (node (ref "IC2") (pin "4") (pinfunction "V-_4") (pintype "passive"))
      (node (ref "ICSP") (pin "6") (pinfunction "6_6") (pintype "passive"))
      (node (ref "J1") (pin "S1") (pinfunction "SH1_S1") (pintype "passive"))
      (node (ref "J1") (pin "S2") (pinfunction "SH2_S2") (pintype "passive"))
      (node (ref "J1") (pin "S3") (pinfunction "SH3_S3") (pintype "passive"))
      (node (ref "J1") (pin "S4") (pinfunction "SH4_S4") (pintype "passive"))
      (node (ref "J1") (pin "S5") (pinfunction "SH5_S5") (pintype "passive"))
      (node (ref "J1") (pin "S6") (pinfunction "SH6_S6") (pintype "passive"))
      (node (ref "J3") (pin "6") (pinfunction "6_6") (pintype "passive"))
      (node (ref "J3") (pin "7") (pinfunction "7_7") (pintype "passive"))
      (node (ref "JP1") (pin "7") (pinfunction "7_7") (pintype "passive"))
      (node (ref "L") (pin "C") (pinfunction "C_C") (pintype "passive"))
      (node (ref "L2") (pin "2") (pinfunction "2_2") (pintype "passive"))
      (node (ref "ON") (pin "C") (pinfunction "C_C") (pintype "passive"))
      (node (ref "R2") (pin "2") (pinfunction "2_2") (pintype "passive"))
      (node (ref "R3") (pin "1") (pinfunction "1_1") (pintype "passive"))
      (node (ref "R4") (pin "1") (pinfunction "1_1") (pintype "passive"))
      (node (ref "RESET") (pin "3") (pinfunction "3_3") (pintype "passive"))
      (node (ref "RESET") (pin "4") (pinfunction "4_4") (pintype "passive"))
      (node (ref "RN1") (pin "2") (pinfunction "1_2") (pintype "passive"))
      (node (ref "RN1") (pin "3") (pinfunction "1_3") (pintype "passive"))
      (node (ref "U1") (pin "15") (pinfunction "GND_15") (pintype "passive"))
      (node (ref "U1") (pin "23") (pinfunction "GND1_23") (pintype "passive"))
      (node (ref "U1") (pin "35") (pinfunction "GND2_35") (pintype "passive"))
      (node (ref "U1") (pin "EXP") (pinfunction "PAD_EXP") (pintype "passive"))
      (node (ref "U2") (pin "15") (pinfunction "GND_15") (pintype "passive"))
      (node (ref "U2") (pin "23") (pinfunction "GND1_23") (pintype "passive"))
      (node (ref "U2") (pin "35") (pinfunction "GND2_35") (pintype "passive"))
      (node (ref "U2") (pin "P$1") (pinfunction "PAD_P$1") (pintype "passive"))
      (node (ref "U3") (pin "2") (pinfunction "GND_2") (pintype "passive"))
      (node (ref "Y1") (pin "2") (pinfunction "GND_2") (pintype "passive"))
      (node (ref "Y1") (pin "4") (pinfunction "GND_4") (pintype "passive"))
      (node (ref "Z1") (pin "2") (pinfunction "2_2") (pintype "passive"))
      (node (ref "Z2") (pin "2") (pinfunction "2_2") (pintype "passive"))
    )
    (net (code "47") (name "Net-(RN2A-2)") (class "Default")
      (node (ref "ON") (pin "A") (pinfunction "A_A") (pintype "passive"))
      (node (ref "RN2") (pin "8") (pinfunction "2_8") (pintype "passive"))
    )
    (net (code "48") (name "Net-(RN2B-2)") (class "Default")
      (node (ref "L") (pin "A") (pinfunction "A_A") (pintype "passive"))
      (node (ref "RN2") (pin "7") (pinfunction "2_7") (pintype "passive"))
    )
    (net (code "49") (name "Net-(RN2C-2)") (class "Default")
      (node (ref "RN2") (pin "6") (pinfunction "2_6") (pintype "passive"))
      (node (ref "TX") (pin "A") (pinfunction "A_A") (pintype "passive"))
    )
    (net (code "50") (name "Net-(RN2D-2)") (class "Default")
      (node (ref "RN2") (pin "5") (pinfunction "2_5") (pintype "passive"))
      (node (ref "RX") (pin "A") (pinfunction "A_A") (pintype "passive"))
    )
    (net (code "51") (name "UGND") (class "Default")
      (node (ref "C7") (pin "2") (pinfunction "2_2") (pintype "passive"))
      (node (ref "J1") (pin "P5") (pinfunction "GND_P5") (pintype "passive"))
      (node (ref "L2") (pin "1") (pinfunction "1_1") (pintype "passive"))
      (node (ref "R3") (pin "2") (pinfunction "2_2") (pintype "passive"))
      (node (ref "U1") (pin "5") (pinfunction "UGND_5") (pintype "passive"))
      (node (ref "U2") (pin "5") (pinfunction "UGND_5") (pintype "passive"))
    )
    (net (code "52") (name "VUSB") (class "Default")
      (node (ref "C8") (pin "+") (pinfunction "+_+") (pintype "passive"))
      (node (ref "C9") (pin "2") (pinfunction "2_2") (pintype "passive"))
      (node (ref "F1") (pin "1") (pinfunction "1_1") (pintype "passive"))
      (node (ref "R4") (pin "2") (pinfunction "2_2") (pintype "passive"))
      (node (ref "T1") (pin "1") (pinfunction "D_1") (pintype "passive"))
      (node (ref "U1") (pin "7") (pinfunction "VBUS_7") (pintype "passive"))
      (node (ref "U2") (pin "7") (pinfunction "VBUS_7") (pintype "passive"))
    )
    (net (code "53") (name "unconnected-(J3-Pad1)") (class "Default")
      (node (ref "J3") (pin "1") (pinfunction "1_1") (pintype "passive"))
    )
    (net (code "54") (name "unconnected-(RESET-5-GND-Pad5)") (class "Default")
      (node (ref "RESET") (pin "5") (pinfunction "5-GND_5") (pintype "passive"))
    )
    (net (code "55") (name "unconnected-(RN3B-1-Pad2)") (class "Default")
      (node (ref "RN3") (pin "2") (pinfunction "1_2") (pintype "passive"))
    )
    (net (code "56") (name "unconnected-(RN3B-2-Pad7)") (class "Default")
      (node (ref "RN3") (pin "7") (pinfunction "2_7") (pintype "passive"))
    )
    (net (code "57") (name "unconnected-(RN3C-1-Pad3)") (class "Default")
      (node (ref "RN3") (pin "3") (pinfunction "1_3") (pintype "passive"))
    )
    (net (code "58") (name "unconnected-(RN3C-2-Pad6)") (class "Default")
      (node (ref "RN3") (pin "6") (pinfunction "2_6") (pintype "passive"))
    )
    (net (code "59") (name "unconnected-(U3-NC{slash}FB-Pad4)") (class "Default")
      (node (ref "U3") (pin "4") (pinfunction "NC/FB_4") (pintype "passive"))
    )
  )
)
